# Clock_Distribution.net
KiCad netlist of a schematic drawn in Altium Designer
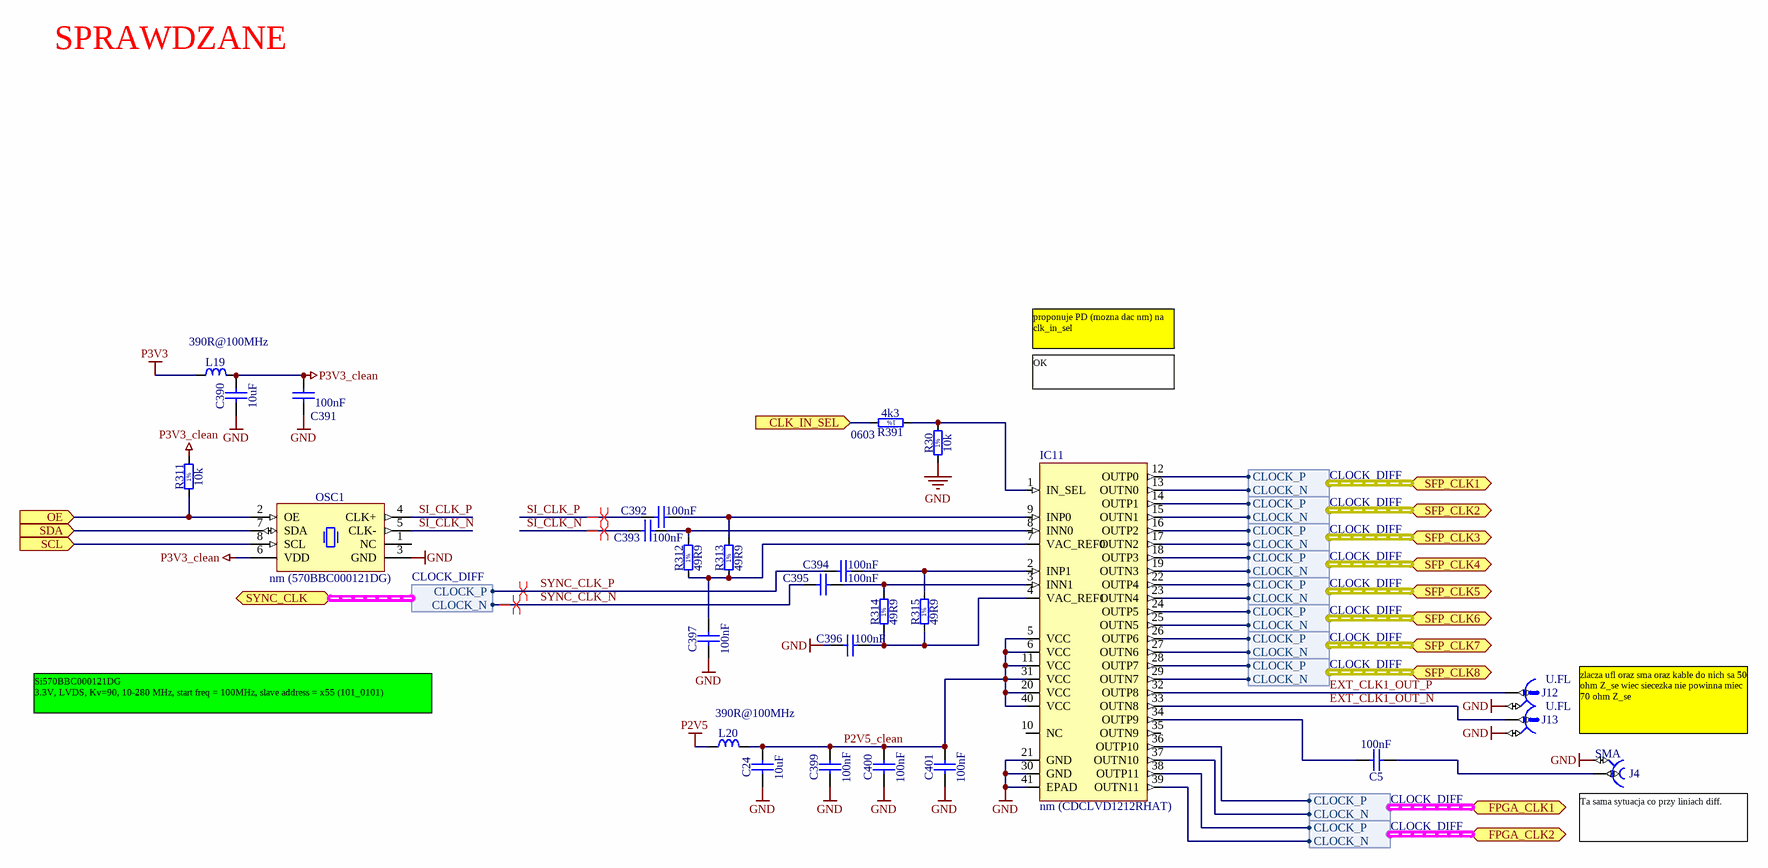
[diagram p0: Clock_Distribution.SchDoc]

(export (version "E")
  (design (tool "Eeschema 10.0.6"))
  (components
    (comp (ref "C5")
      (value "100nF")
      (footprint "CAPC1005X55N")
      (description "Non-polarised capacitor")
      (fields
        (field (name "PART NUMBER") "CC0402_100NF_16V_10%_X7R")
        (field (name "VOLTAGE") "16V")
        (field (name "AUTHOR") "CERN DEM JLC")
      )
      (libsource (lib "Capacitors") (part "Capacitor - non polarized"))
    )
    (comp (ref "C24")
      (value "10uF")
      (footprint "CAPC2012X135N")
      (description "Non-polarised capacitor")
      (fields
        (field (name "PART NUMBER") "CC0805_10UF_10V_10%_X7R")
        (field (name "VOLTAGE") "10V")
        (field (name "AUTHOR") "CERN DEM JLC")
      )
      (libsource (lib "Capacitors") (part "Capacitor - non polarized"))
    )
    (comp (ref "C390")
      (value "10uF")
      (footprint "CAPC2012X135N")
      (description "Non-polarised capacitor")
      (fields
        (field (name "PART NUMBER") "CC0805_10UF_10V_10%_X7R")
        (field (name "VOLTAGE") "10V")
        (field (name "AUTHOR") "CERN DEM JLC")
      )
      (libsource (lib "Capacitors") (part "Capacitor - non polarized"))
    )
    (comp (ref "C391")
      (value "100nF")
      (footprint "CAPC0603X33N")
      (description "Non-polarised capacitor")
      (fields
        (field (name "PART NUMBER") "CC0201_100NF_6.3V_10%_X5R")
        (field (name "VOLTAGE") "6.3V")
        (field (name "AUTHOR") "CERN DEM JLC")
      )
      (libsource (lib "Capacitors") (part "Capacitor - non polarized"))
    )
    (comp (ref "C392")
      (value "100nF")
      (footprint "CAPC0603X33N")
      (description "Non-polarised capacitor")
      (fields
        (field (name "PART NUMBER") "CC0201_100NF_6.3V_10%_X5R")
        (field (name "VOLTAGE") "6.3V")
        (field (name "AUTHOR") "CERN DEM JLC")
      )
      (libsource (lib "Capacitors") (part "Capacitor - non polarized"))
    )
    (comp (ref "C393")
      (value "100nF")
      (footprint "CAPC0603X33N")
      (description "Non-polarised capacitor")
      (fields
        (field (name "PART NUMBER") "CC0201_100NF_6.3V_10%_X5R")
        (field (name "VOLTAGE") "6.3V")
        (field (name "AUTHOR") "CERN DEM JLC")
      )
      (libsource (lib "Capacitors") (part "Capacitor - non polarized"))
    )
    (comp (ref "C394")
      (value "100nF")
      (footprint "CAPC0603X33N")
      (description "Non-polarised capacitor")
      (fields
        (field (name "PART NUMBER") "CC0201_100NF_6.3V_10%_X5R")
        (field (name "VOLTAGE") "6.3V")
        (field (name "AUTHOR") "CERN DEM JLC")
      )
      (libsource (lib "Capacitors") (part "Capacitor - non polarized"))
    )
    (comp (ref "C395")
      (value "100nF")
      (footprint "CAPC0603X33N")
      (description "Non-polarised capacitor")
      (fields
        (field (name "PART NUMBER") "CC0201_100NF_6.3V_10%_X5R")
        (field (name "VOLTAGE") "6.3V")
        (field (name "AUTHOR") "CERN DEM JLC")
      )
      (libsource (lib "Capacitors") (part "Capacitor - non polarized"))
    )
    (comp (ref "C396")
      (value "100nF")
      (footprint "CAPC0603X33N")
      (description "Non-polarised capacitor")
      (fields
        (field (name "PART NUMBER") "CC0201_100NF_6.3V_10%_X5R")
        (field (name "VOLTAGE") "6.3V")
        (field (name "AUTHOR") "CERN DEM JLC")
      )
      (libsource (lib "Capacitors") (part "Capacitor - non polarized"))
    )
    (comp (ref "C397")
      (value "100nF")
      (footprint "CAPC0603X33N")
      (description "Non-polarised capacitor")
      (fields
        (field (name "PART NUMBER") "CC0201_100NF_6.3V_10%_X5R")
        (field (name "VOLTAGE") "6.3V")
        (field (name "AUTHOR") "CERN DEM JLC")
      )
      (libsource (lib "Capacitors") (part "Capacitor - non polarized"))
    )
    (comp (ref "C399")
      (value "100nF")
      (footprint "CAPC0603X33N")
      (description "Non-polarised capacitor")
      (fields
        (field (name "PART NUMBER") "CC0201_100NF_6.3V_10%_X5R")
        (field (name "VOLTAGE") "6.3V")
        (field (name "AUTHOR") "CERN DEM JLC")
      )
      (libsource (lib "Capacitors") (part "Capacitor - non polarized"))
    )
    (comp (ref "C400")
      (value "100nF")
      (footprint "CAPC0603X33N")
      (description "Non-polarised capacitor")
      (fields
        (field (name "PART NUMBER") "CC0201_100NF_6.3V_10%_X5R")
        (field (name "VOLTAGE") "6.3V")
        (field (name "AUTHOR") "CERN DEM JLC")
      )
      (libsource (lib "Capacitors") (part "Capacitor - non polarized"))
    )
    (comp (ref "C401")
      (value "100nF")
      (footprint "CAPC0603X33N")
      (description "Non-polarised capacitor")
      (fields
        (field (name "PART NUMBER") "CC0201_100NF_6.3V_10%_X5R")
        (field (name "VOLTAGE") "6.3V")
        (field (name "AUTHOR") "CERN DEM JLC")
      )
      (libsource (lib "Capacitors") (part "Capacitor - non polarized"))
    )
    (comp (ref "IC11")
      (value "nm (CDCLVD1212RHAT)")
      (footprint "QFN50P600-40")
      (description "Low Jitter, 2-Input Selectable 1:12 Universal-to-LVDS Buffer")
      (libsource (lib "LIBRARY_SCH") (part "CLOCK_CDCLVD1212"))
    )
    (comp (ref "J4")
      (value "SMA")
      (footprint "HUBER-SUHNER_85 SMA-50-0-101/111 NE")
      (fields
        (field (name "PART NUMBER") "HUBER-SUHNER_85_SMA-50-0-101/111_NE")
        (field (name "MANUFACTURER") "HUBER+SUHNER")
        (field (name "MANUFACTURER PART NUMBER") "85_SMA-50-0-101/111_NE")
        (field (name "AUTHOR") "CERN DEM JLC")
      )
      (libsource (lib "Connectors") (part "Coax_1Female_1Shield"))
    )
    (comp (ref "J12")
      (value "U.FL")
      (footprint "HIROSE_U.FL-R-SMT-1(10)")
      (fields
        (field (name "PART NUMBER") "HIROSE_U.FL-R-SMT-1(10)")
        (field (name "MANUFACTURER") "HIROSE (HRS)")
        (field (name "MANUFACTURER PART NUMBER") "U.FL-R-SMT-1(10)")
        (field (name "AUTHOR") "CERN DEM JLC")
      )
      (libsource (lib "Connectors") (part "Coax_1Male_1Shield"))
    )
    (comp (ref "J13")
      (value "U.FL")
      (footprint "HIROSE_U.FL-R-SMT-1(10)")
      (fields
        (field (name "PART NUMBER") "HIROSE_U.FL-R-SMT-1(10)")
        (field (name "MANUFACTURER") "HIROSE (HRS)")
        (field (name "MANUFACTURER PART NUMBER") "U.FL-R-SMT-1(10)")
        (field (name "AUTHOR") "CERN DEM JLC")
      )
      (libsource (lib "Connectors") (part "Coax_1Male_1Shield"))
    )
    (comp (ref "L19")
      (value "390R@100MHz")
      (footprint "INDC1608X95N")
      (description "Inductor")
      (fields
        (field (name "PART NUMBER") "IND0603_TDK_MPZ1608R391A")
        (field (name "POWER") "1.2A")
        (field (name "AUTHOR") "CERN DEM JLC")
      )
      (libsource (lib "Inductors & Transformers") (part "Inductor"))
    )
    (comp (ref "L20")
      (value "390R@100MHz")
      (footprint "INDC1608X95N")
      (description "Inductor")
      (fields
        (field (name "PART NUMBER") "IND0603_TDK_MPZ1608R391A")
        (field (name "POWER") "1.2A")
        (field (name "AUTHOR") "CERN DEM JLC")
      )
      (libsource (lib "Inductors & Transformers") (part "Inductor"))
    )
    (comp (ref "OSC1")
      (value "nm (570BBC000121DG)")
      (footprint "OSC_SILICON-LAB_SI570")
      (description "Any-Rate I2C Programmable XO Oscillator Si570 Serie")
      (fields
        (field (name "PART NUMBER") "OSC_10-280MHZ_SILICON-LAB_Si570BBC000121DG")
        (field (name "MANUFACTURER") "SILICON LABS")
        (field (name "AUTHOR") "CERN DEM JLC")
      )
      (libsource (lib "ICs And Semiconductors") (part "Oscillator SILICON-LAB_Si570"))
    )
    (comp (ref "R30")
      (value "10k")
      (footprint "RESC1005X40N")
      (description "Resistor - 1%")
      (fields
        (field (name "PART NUMBER") "R0402_10K_1%_0.0625W_100PPM")
        (field (name "POWER") "0.0625W")
        (field (name "AUTHOR") "CERN DEM JLC")
      )
      (libsource (lib "Resistors") (part "Resistor - 1%"))
    )
    (comp (ref "R311")
      (value "10k")
      (footprint "RESC1005X40N")
      (description "Resistor - 1%")
      (fields
        (field (name "PART NUMBER") "R0402_10K_1%_0.0625W_100PPM")
        (field (name "POWER") "0.0625W")
        (field (name "AUTHOR") "CERN DEM JLC")
      )
      (libsource (lib "Resistors") (part "Resistor - 1%"))
    )
    (comp (ref "R312")
      (value "49R9")
      (footprint "RESC1005X40N")
      (description "Resistor - 1%")
      (fields
        (field (name "PART NUMBER") "R0402_49R9_1%_0.0625W_100PPM")
        (field (name "POWER") "0.0625W")
        (field (name "AUTHOR") "CERN DEM JLC")
      )
      (libsource (lib "Resistors") (part "Resistor - 1%"))
    )
    (comp (ref "R313")
      (value "49R9")
      (footprint "RESC1005X40N")
      (description "Resistor - 1%")
      (fields
        (field (name "PART NUMBER") "R0402_49R9_1%_0.0625W_100PPM")
        (field (name "POWER") "0.0625W")
        (field (name "AUTHOR") "CERN DEM JLC")
      )
      (libsource (lib "Resistors") (part "Resistor - 1%"))
    )
    (comp (ref "R314")
      (value "49R9")
      (footprint "RESC1005X40N")
      (description "Resistor - 1%")
      (fields
        (field (name "PART NUMBER") "R0402_49R9_1%_0.0625W_100PPM")
        (field (name "POWER") "0.0625W")
        (field (name "AUTHOR") "CERN DEM JLC")
      )
      (libsource (lib "Resistors") (part "Resistor - 1%"))
    )
    (comp (ref "R315")
      (value "49R9")
      (footprint "RESC1005X40N")
      (description "Resistor - 1%")
      (fields
        (field (name "PART NUMBER") "R0402_49R9_1%_0.0625W_100PPM")
        (field (name "POWER") "0.0625W")
        (field (name "AUTHOR") "CERN DEM JLC")
      )
      (libsource (lib "Resistors") (part "Resistor - 1%"))
    )
    (comp (ref "R391")
      (value "4k3")
      (footprint "RESC1608X55N")
      (description "Resistor - 1%")
      (fields
        (field (name "PART NUMBER") "R0603_4K3_1%_0.1W_100PPM")
        (field (name "POWER") "0.1W")
        (field (name "CASE") "0603")
        (field (name "AUTHOR") "CERN DEM JLC")
      )
      (libsource (lib "Resistors") (part "Resistor - 1%"))
    )
  )
  (nets
    (net (code "3") (name "/CLK_IN_SEL") (class "Default")
      (node (ref "R391") (pin "2") (pinfunction "2_2") (pintype "passive"))
    )
    (net (code "4") (name "/EXT_CLK1_OUT_N") (class "Default")
      (node (ref "IC11") (pin "33") (pinfunction "OUTN8_33") (pintype "output"))
      (node (ref "J13") (pin "1") (pinfunction "1_1") (pintype "bidirectional"))
    )
    (net (code "5") (name "/EXT_CLK1_OUT_P") (class "Default")
      (node (ref "IC11") (pin "32") (pinfunction "OUTP8_32") (pintype "output"))
      (node (ref "J12") (pin "1") (pinfunction "1_1") (pintype "bidirectional"))
    )
    (net (code "6") (name "/OE") (class "Default")
      (node (ref "OSC1") (pin "2") (pinfunction "OE_2") (pintype "input"))
      (node (ref "R311") (pin "1") (pinfunction "1_1") (pintype "passive"))
    )
    (net (code "7") (name "/P2V5_clean") (class "Default")
      (node (ref "C24") (pin "2") (pinfunction "2_2") (pintype "passive"))
      (node (ref "C399") (pin "2") (pinfunction "2_2") (pintype "passive"))
      (node (ref "C400") (pin "2") (pinfunction "2_2") (pintype "passive"))
      (node (ref "C401") (pin "2") (pinfunction "2_2") (pintype "passive"))
      (node (ref "IC11") (pin "11") (pinfunction "VCC_11") (pintype "power_in"))
      (node (ref "IC11") (pin "20") (pinfunction "VCC_20") (pintype "power_in"))
      (node (ref "IC11") (pin "31") (pinfunction "VCC_31") (pintype "power_in"))
      (node (ref "IC11") (pin "40") (pinfunction "VCC_40") (pintype "power_in"))
      (node (ref "IC11") (pin "5") (pinfunction "VCC_5") (pintype "power_in"))
      (node (ref "IC11") (pin "6") (pinfunction "VCC_6") (pintype "power_in"))
      (node (ref "L20") (pin "2") (pinfunction "2_2") (pintype "passive"))
    )
    (net (code "8") (name "/SCL") (class "Default")
      (node (ref "OSC1") (pin "8") (pinfunction "SCL_8") (pintype "input"))
    )
    (net (code "9") (name "/SDA") (class "Default")
      (node (ref "OSC1") (pin "7") (pinfunction "SDA_7") (pintype "bidirectional"))
    )
    (net (code "11") (name "/SI_CLK_N") (class "Default")
      (node (ref "C393") (pin "2") (pinfunction "2_2") (pintype "passive"))
      (node (ref "OSC1") (pin "5") (pinfunction "CLK-_5") (pintype "output"))
    )
    (net (code "12") (name "/SI_CLK_P") (class "Default")
      (node (ref "C392") (pin "2") (pinfunction "2_2") (pintype "passive"))
      (node (ref "OSC1") (pin "4") (pinfunction "CLK+_4") (pintype "output"))
    )
    (net (code "13") (name "/SYNC_CLK_N") (class "Default")
      (node (ref "C395") (pin "2") (pinfunction "2_2") (pintype "passive"))
    )
    (net (code "14") (name "/SYNC_CLK_P") (class "Default")
      (node (ref "C394") (pin "2") (pinfunction "2_2") (pintype "passive"))
    )
    (net (code "16") (name "GND") (class "Default")
      (node (ref "C24") (pin "1") (pinfunction "1_1") (pintype "passive"))
      (node (ref "C390") (pin "1") (pinfunction "1_1") (pintype "passive"))
      (node (ref "C391") (pin "1") (pinfunction "1_1") (pintype "passive"))
      (node (ref "C396") (pin "1") (pinfunction "1_1") (pintype "passive"))
      (node (ref "C397") (pin "1") (pinfunction "1_1") (pintype "passive"))
      (node (ref "C399") (pin "1") (pinfunction "1_1") (pintype "passive"))
      (node (ref "C400") (pin "1") (pinfunction "1_1") (pintype "passive"))
      (node (ref "C401") (pin "1") (pinfunction "1_1") (pintype "passive"))
      (node (ref "IC11") (pin "21") (pinfunction "GND_21") (pintype "power_in"))
      (node (ref "IC11") (pin "30") (pinfunction "GND_30") (pintype "power_in"))
      (node (ref "IC11") (pin "41") (pinfunction "EPAD_41") (pintype "power_in"))
      (node (ref "J12") (pin "2") (pinfunction "2_2") (pintype "bidirectional"))
      (node (ref "J13") (pin "2") (pinfunction "2_2") (pintype "bidirectional"))
      (node (ref "J4") (pin "2") (pinfunction "2_2") (pintype "bidirectional"))
      (node (ref "OSC1") (pin "3") (pinfunction "GND_3") (pintype "power_in"))
      (node (ref "R30") (pin "1") (pinfunction "1_1") (pintype "passive"))
    )
    (net (code "17") (name "Net-(C5-Pad2)") (class "Default")
      (node (ref "C5") (pin "2") (pinfunction "2_2") (pintype "passive"))
      (node (ref "J4") (pin "1") (pinfunction "1_1") (pintype "bidirectional"))
    )
    (net (code "18") (name "Net-(IC11-INN0)") (class "Default")
      (node (ref "C393") (pin "1") (pinfunction "1_1") (pintype "passive"))
      (node (ref "IC11") (pin "8") (pinfunction "INN0_8") (pintype "input"))
      (node (ref "R312") (pin "2") (pinfunction "2_2") (pintype "passive"))
    )
    (net (code "19") (name "Net-(IC11-INN1)") (class "Default")
      (node (ref "C395") (pin "1") (pinfunction "1_1") (pintype "passive"))
      (node (ref "IC11") (pin "3") (pinfunction "INN1_3") (pintype "input"))
      (node (ref "R314") (pin "2") (pinfunction "2_2") (pintype "passive"))
    )
    (net (code "20") (name "Net-(IC11-INP0)") (class "Default")
      (node (ref "C392") (pin "1") (pinfunction "1_1") (pintype "passive"))
      (node (ref "IC11") (pin "9") (pinfunction "INP0_9") (pintype "input"))
      (node (ref "R313") (pin "2") (pinfunction "2_2") (pintype "passive"))
    )
    (net (code "21") (name "Net-(IC11-INP1)") (class "Default")
      (node (ref "C394") (pin "1") (pinfunction "1_1") (pintype "passive"))
      (node (ref "IC11") (pin "2") (pinfunction "INP1_2") (pintype "input"))
      (node (ref "R315") (pin "2") (pinfunction "2_2") (pintype "passive"))
    )
    (net (code "22") (name "Net-(IC11-IN_SEL)") (class "Default")
      (node (ref "IC11") (pin "1") (pinfunction "IN_SEL_1") (pintype "input"))
      (node (ref "R30") (pin "2") (pinfunction "2_2") (pintype "passive"))
      (node (ref "R391") (pin "1") (pinfunction "1_1") (pintype "passive"))
    )
    (net (code "23") (name "Net-(IC11-OUTP9)") (class "Default")
      (node (ref "C5") (pin "1") (pinfunction "1_1") (pintype "passive"))
      (node (ref "IC11") (pin "34") (pinfunction "OUTP9_34") (pintype "output"))
    )
    (net (code "24") (name "Net-(IC11-VAC_REF0)") (class "Default")
      (node (ref "C397") (pin "2") (pinfunction "2_2") (pintype "passive"))
      (node (ref "IC11") (pin "7") (pinfunction "VAC_REF0_7") (pintype "power_in"))
      (node (ref "R312") (pin "1") (pinfunction "1_1") (pintype "passive"))
      (node (ref "R313") (pin "1") (pinfunction "1_1") (pintype "passive"))
    )
    (net (code "25") (name "Net-(IC11-VAC_REF1)") (class "Default")
      (node (ref "C396") (pin "2") (pinfunction "2_2") (pintype "passive"))
      (node (ref "IC11") (pin "4") (pinfunction "VAC_REF1_4") (pintype "power_in"))
      (node (ref "R314") (pin "1") (pinfunction "1_1") (pintype "passive"))
      (node (ref "R315") (pin "1") (pinfunction "1_1") (pintype "passive"))
    )
    (net (code "26") (name "P2V5") (class "Default")
      (node (ref "L20") (pin "1") (pinfunction "1_1") (pintype "passive"))
    )
    (net (code "27") (name "P3V3") (class "Default")
      (node (ref "L19") (pin "1") (pinfunction "1_1") (pintype "passive"))
    )
    (net (code "28") (name "P3V3_clean") (class "Default")
      (node (ref "C390") (pin "2") (pinfunction "2_2") (pintype "passive"))
      (node (ref "C391") (pin "2") (pinfunction "2_2") (pintype "passive"))
      (node (ref "L19") (pin "2") (pinfunction "2_2") (pintype "passive"))
      (node (ref "OSC1") (pin "6") (pinfunction "VDD_6") (pintype "power_in"))
      (node (ref "R311") (pin "2") (pinfunction "2_2") (pintype "passive"))
    )
    (net (code "29") (name "unconnected-(IC11-NC-Pad10)") (class "Default")
      (node (ref "IC11") (pin "10") (pinfunction "NC_10") (pintype "passive"))
    )
    (net (code "30") (name "unconnected-(IC11-OUTN0-Pad13)") (class "Default")
      (node (ref "IC11") (pin "13") (pinfunction "OUTN0_13") (pintype "output"))
    )
    (net (code "31") (name "unconnected-(IC11-OUTN1-Pad15)") (class "Default")
      (node (ref "IC11") (pin "15") (pinfunction "OUTN1_15") (pintype "output"))
    )
    (net (code "32") (name "unconnected-(IC11-OUTN2-Pad17)") (class "Default")
      (node (ref "IC11") (pin "17") (pinfunction "OUTN2_17") (pintype "output"))
    )
    (net (code "33") (name "unconnected-(IC11-OUTN3-Pad19)") (class "Default")
      (node (ref "IC11") (pin "19") (pinfunction "OUTN3_19") (pintype "output"))
    )
    (net (code "34") (name "unconnected-(IC11-OUTN4-Pad23)") (class "Default")
      (node (ref "IC11") (pin "23") (pinfunction "OUTN4_23") (pintype "output"))
    )
    (net (code "35") (name "unconnected-(IC11-OUTN5-Pad25)") (class "Default")
      (node (ref "IC11") (pin "25") (pinfunction "OUTN5_25") (pintype "output"))
    )
    (net (code "36") (name "unconnected-(IC11-OUTN6-Pad27)") (class "Default")
      (node (ref "IC11") (pin "27") (pinfunction "OUTN6_27") (pintype "output"))
    )
    (net (code "37") (name "unconnected-(IC11-OUTN7-Pad29)") (class "Default")
      (node (ref "IC11") (pin "29") (pinfunction "OUTN7_29") (pintype "output"))
    )
    (net (code "38") (name "unconnected-(IC11-OUTN9-Pad35)") (class "Default")
      (node (ref "IC11") (pin "35") (pinfunction "OUTN9_35") (pintype "output"))
    )
    (net (code "39") (name "unconnected-(IC11-OUTN10-Pad37)") (class "Default")
      (node (ref "IC11") (pin "37") (pinfunction "OUTN10_37") (pintype "output"))
    )
    (net (code "40") (name "unconnected-(IC11-OUTN11-Pad39)") (class "Default")
      (node (ref "IC11") (pin "39") (pinfunction "OUTN11_39") (pintype "output"))
    )
    (net (code "41") (name "unconnected-(IC11-OUTP0-Pad12)") (class "Default")
      (node (ref "IC11") (pin "12") (pinfunction "OUTP0_12") (pintype "output"))
    )
    (net (code "42") (name "unconnected-(IC11-OUTP1-Pad14)") (class "Default")
      (node (ref "IC11") (pin "14") (pinfunction "OUTP1_14") (pintype "output"))
    )
    (net (code "43") (name "unconnected-(IC11-OUTP2-Pad16)") (class "Default")
      (node (ref "IC11") (pin "16") (pinfunction "OUTP2_16") (pintype "output"))
    )
    (net (code "44") (name "unconnected-(IC11-OUTP3-Pad18)") (class "Default")
      (node (ref "IC11") (pin "18") (pinfunction "OUTP3_18") (pintype "output"))
    )
    (net (code "45") (name "unconnected-(IC11-OUTP4-Pad22)") (class "Default")
      (node (ref "IC11") (pin "22") (pinfunction "OUTP4_22") (pintype "output"))
    )
    (net (code "46") (name "unconnected-(IC11-OUTP5-Pad24)") (class "Default")
      (node (ref "IC11") (pin "24") (pinfunction "OUTP5_24") (pintype "output"))
    )
    (net (code "47") (name "unconnected-(IC11-OUTP6-Pad26)") (class "Default")
      (node (ref "IC11") (pin "26") (pinfunction "OUTP6_26") (pintype "output"))
    )
    (net (code "48") (name "unconnected-(IC11-OUTP7-Pad28)") (class "Default")
      (node (ref "IC11") (pin "28") (pinfunction "OUTP7_28") (pintype "output"))
    )
    (net (code "49") (name "unconnected-(IC11-OUTP10-Pad36)") (class "Default")
      (node (ref "IC11") (pin "36") (pinfunction "OUTP10_36") (pintype "output"))
    )
    (net (code "50") (name "unconnected-(IC11-OUTP11-Pad38)") (class "Default")
      (node (ref "IC11") (pin "38") (pinfunction "OUTP11_38") (pintype "output"))
    )
    (net (code "51") (name "unconnected-(OSC1-NC-Pad1)") (class "Default")
      (node (ref "OSC1") (pin "1") (pinfunction "NC_1") (pintype "passive"))
    )
  )
)
